# Zio_Qwiic_Eink_Display_Red_2_9.net
KiCad netlist of a schematic drawn in EAGLE
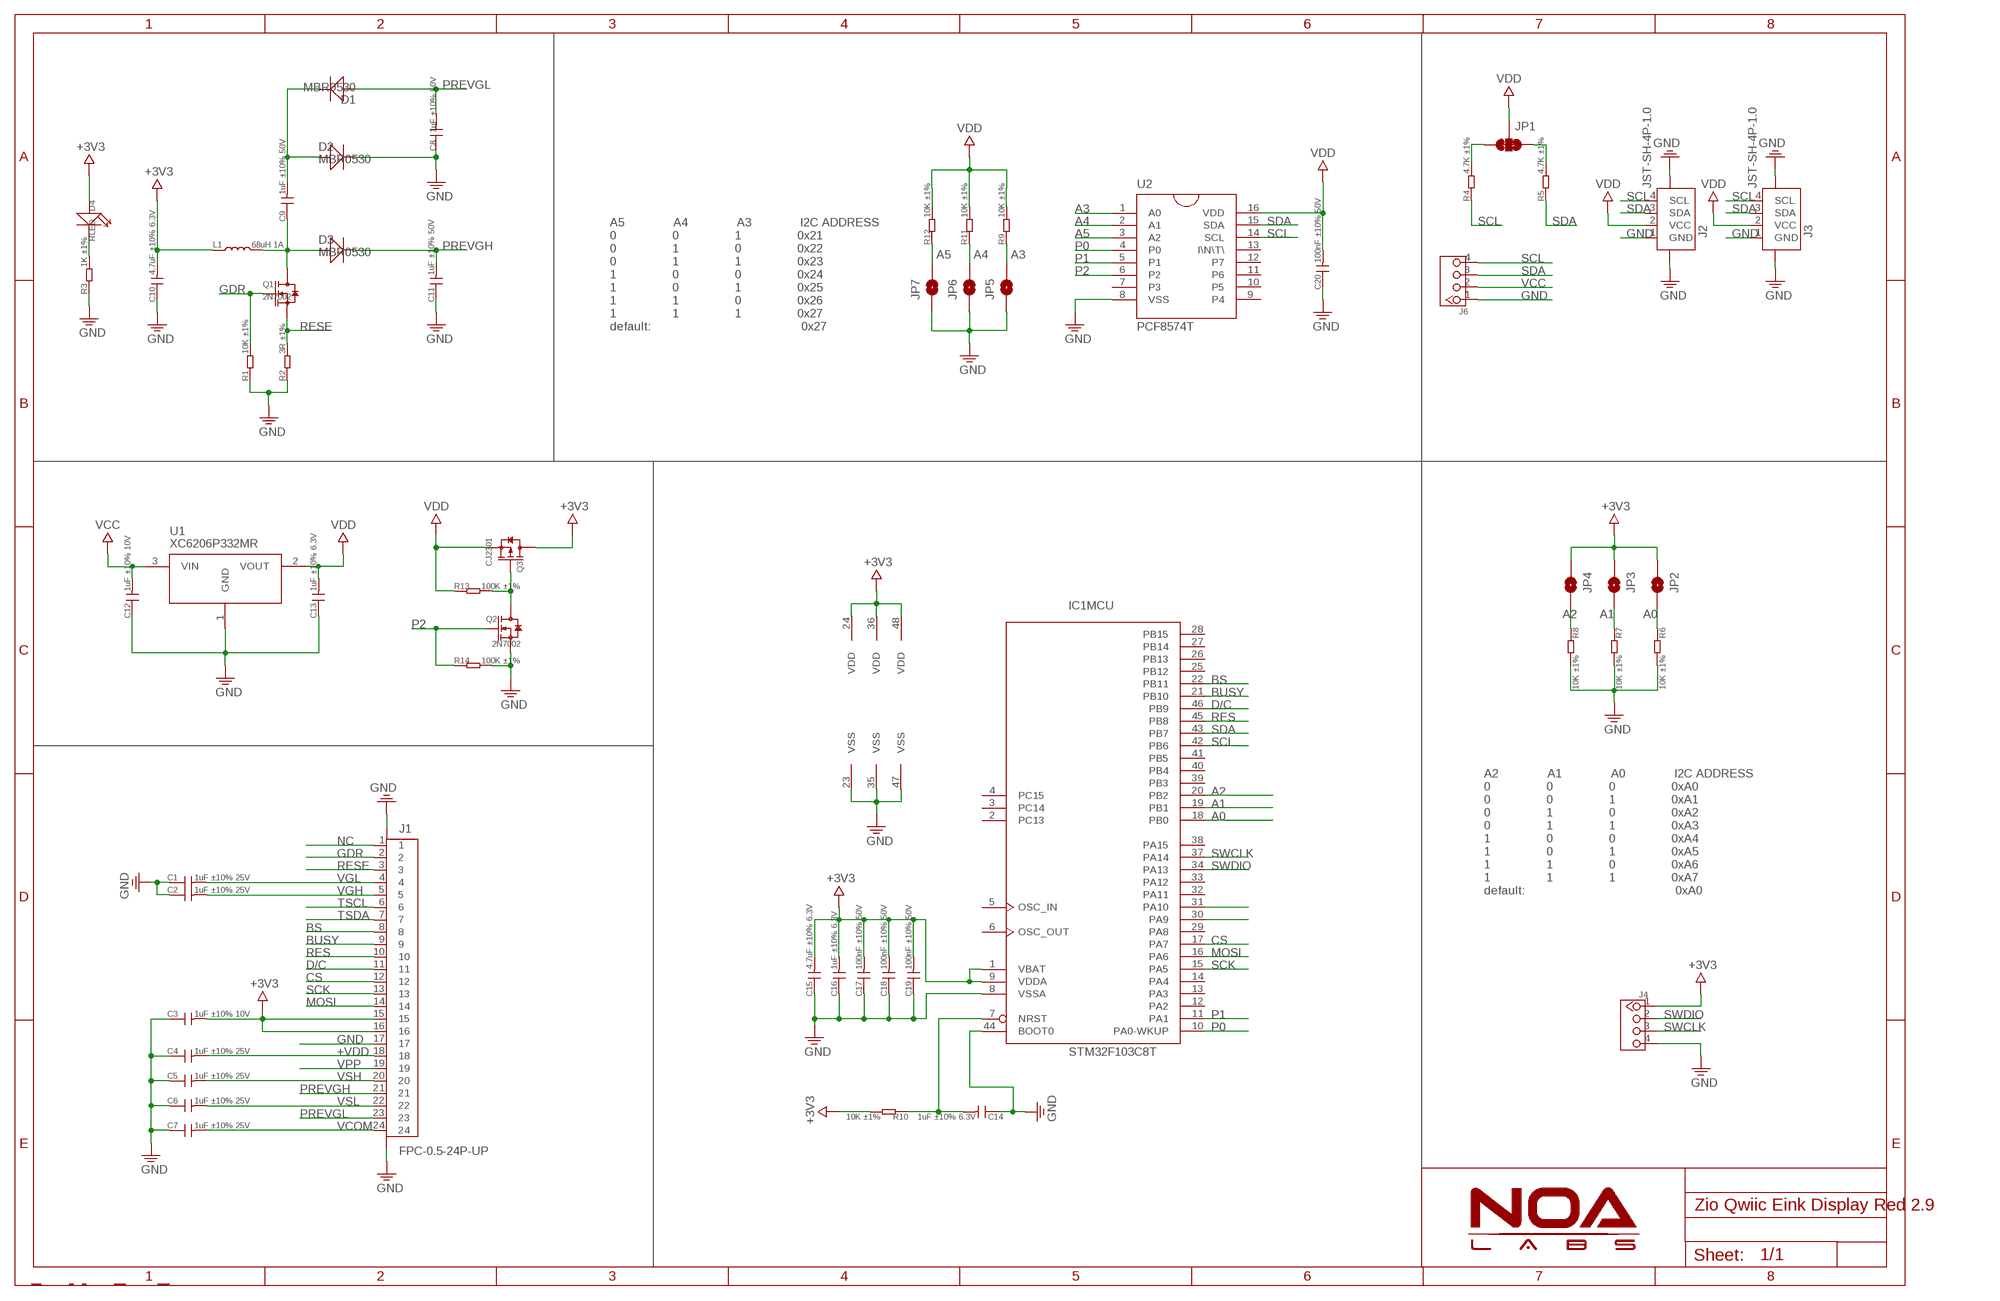
[diagram p0: schematic, sheet 1]

(export (version "E")
  (design (tool "Eeschema 10.0.6"))
  (components
    (comp (ref "C1")
      (value "1uF ±10% 25V")
      (footprint "eagle-import:C0603")
      (libsource (lib "eagle-import") (part "RCL_1838970_C-0603"))
    )
    (comp (ref "C2")
      (value "1uF ±10% 25V")
      (footprint "eagle-import:C0603")
      (libsource (lib "eagle-import") (part "RCL_1838970_C-0603"))
    )
    (comp (ref "C3")
      (value "1uF ±10% 10V")
      (footprint "eagle-import:C0603")
      (libsource (lib "eagle-import") (part "RCL_1838970_C-0603"))
    )
    (comp (ref "C4")
      (value "1uF ±10% 25V")
      (footprint "eagle-import:C0603")
      (libsource (lib "eagle-import") (part "RCL_1838970_C-0603"))
    )
    (comp (ref "C5")
      (value "1uF ±10% 25V")
      (footprint "eagle-import:C0603")
      (libsource (lib "eagle-import") (part "RCL_1838970_C-0603"))
    )
    (comp (ref "C6")
      (value "1uF ±10% 25V")
      (footprint "eagle-import:C0603")
      (libsource (lib "eagle-import") (part "RCL_1838970_C-0603"))
    )
    (comp (ref "C7")
      (value "1uF ±10% 25V")
      (footprint "eagle-import:C0603")
      (libsource (lib "eagle-import") (part "RCL_1838970_C-0603"))
    )
    (comp (ref "C8")
      (value "1uF ±10% 50V")
      (footprint "eagle-import:0603")
      (libsource (lib "eagle-import") (part "C-0603"))
    )
    (comp (ref "C9")
      (value "1uF ±10% 50V")
      (footprint "eagle-import:C0603")
      (libsource (lib "eagle-import") (part "RCL_1838970_C-0603"))
    )
    (comp (ref "C10")
      (value "4.7uF ±10% 6.3V")
      (footprint "eagle-import:C0603")
      (libsource (lib "eagle-import") (part "RCL_1838970_C-0603"))
    )
    (comp (ref "C11")
      (value "1uF ±10% 50V")
      (footprint "eagle-import:C0603")
      (libsource (lib "eagle-import") (part "RCL_1838970_C-0603"))
    )
    (comp (ref "C12")
      (value "1uF ±10% 10V")
      (footprint "eagle-import:C0603")
      (libsource (lib "eagle-import") (part "RCL_1838970_C-0603"))
    )
    (comp (ref "C13")
      (value "1uF ±10% 6.3V")
      (footprint "eagle-import:C0603")
      (libsource (lib "eagle-import") (part "RCL_1838970_C-0603"))
    )
    (comp (ref "C14")
      (value "1uF ±10% 6.3V")
      (footprint "eagle-import:C0603")
      (libsource (lib "eagle-import") (part "RCL_1838970_C-0603"))
    )
    (comp (ref "C15")
      (value "4.7uF ±10% 6.3V")
      (footprint "eagle-import:C0603")
      (libsource (lib "eagle-import") (part "RCL_1838970_C-0603"))
    )
    (comp (ref "C16")
      (value "1uF ±10% 6.3V")
      (footprint "eagle-import:C0603")
      (libsource (lib "eagle-import") (part "RCL_1838970_C-0603"))
    )
    (comp (ref "C17")
      (value "100nF ±10% 50V")
      (footprint "eagle-import:C0603")
      (libsource (lib "eagle-import") (part "RCL_1838970_C-0603"))
    )
    (comp (ref "C18")
      (value "100nF ±10% 50V")
      (footprint "eagle-import:C0603")
      (libsource (lib "eagle-import") (part "RCL_1838970_C-0603"))
    )
    (comp (ref "C19")
      (value "100nF ±10% 50V")
      (footprint "eagle-import:C0603")
      (libsource (lib "eagle-import") (part "RCL_1838970_C-0603"))
    )
    (comp (ref "C20")
      (value "100nF ±10% 50V")
      (footprint "eagle-import:C0603")
      (libsource (lib "eagle-import") (part "RCL_1838970_C-0603"))
    )
    (comp (ref "D1")
      (value "MBR0530")
      (footprint "eagle-import:SOD123")
      (libsource (lib "eagle-import") (part "D'1206'"))
    )
    (comp (ref "D2")
      (value "MBR0530")
      (footprint "eagle-import:SOD123")
      (libsource (lib "eagle-import") (part "D'1206'"))
    )
    (comp (ref "D3")
      (value "MBR0530")
      (footprint "eagle-import:SOD123")
      (libsource (lib "eagle-import") (part "D'1206'"))
    )
    (comp (ref "D4")
      (value "RLED")
      (footprint "eagle-import:LED-0603")
      (libsource (lib "eagle-import") (part "LED'0603'"))
    )
    (comp (ref "IC1")
      (value "STM32F103C8T")
      (footprint "eagle-import:LQFP48")
      (libsource (lib "eagle-import") (part "STM32F103CT8"))
    )
    (comp (ref "J1")
      (value "FPC-0.5-24P-UP")
      (footprint "eagle-import:FPC-0.5-24P_UP")
      (libsource (lib "eagle-import") (part "FPC-0.5-24P-UP"))
    )
    (comp (ref "J2")
      (value "JST-SH-4P-1.0")
      (footprint "eagle-import:JST-SH-4P")
      (libsource (lib "eagle-import") (part "JST-SH-4P-1.0"))
    )
    (comp (ref "J3")
      (value "JST-SH-4P-1.0")
      (footprint "eagle-import:JST-SH-4P")
      (libsource (lib "eagle-import") (part "JST-SH-4P-1.0"))
    )
    (comp (ref "J4")
      (value "HEADER-4P-2.54-SMD")
      (footprint "eagle-import:4P-2.54-SMD-180")
      (libsource (lib "eagle-import") (part "HEADER-4P-2.54-SMD"))
    )
    (comp (ref "J6")
      (value "HEADER-4P-60/35MIL")
      (footprint "eagle-import:4P-65_35MIL")
      (libsource (lib "eagle-import") (part "Connector_NOA_1982094_HEADER-4P-60/35MIL"))
    )
    (comp (ref "JP1")
      (value "SMT-JUMPER_3_2-NC_TRACE")
      (footprint "eagle-import:SMT-JUMPER_3_2-NC_TRACE")
      (libsource (lib "eagle-import") (part "SMT-JUMPER_3_2-NC_TRACE"))
    )
    (comp (ref "JP2")
      (value "JUMPER-SMT_2_NC_PASTE_NOCREM")
      (footprint "eagle-import:SMT-JUMPER_2_NC_PASTE_SILK_NOCREM")
      (libsource (lib "eagle-import") (part "JUMPER-SMT_2_NC_PASTE_NOCREM"))
    )
    (comp (ref "JP3")
      (value "JUMPER-SMT_2_NC_PASTE_NOCREM")
      (footprint "eagle-import:SMT-JUMPER_2_NC_PASTE_SILK_NOCREM")
      (libsource (lib "eagle-import") (part "JUMPER-SMT_2_NC_PASTE_NOCREM"))
    )
    (comp (ref "JP4")
      (value "JUMPER-SMT_2_NC_PASTE_NOCREM")
      (footprint "eagle-import:SMT-JUMPER_2_NC_PASTE_SILK_NOCREM")
      (libsource (lib "eagle-import") (part "JUMPER-SMT_2_NC_PASTE_NOCREM"))
    )
    (comp (ref "JP5")
      (value "JUMPER-SMT_2_NC_PASTE_NOCREM")
      (footprint "eagle-import:SMT-JUMPER_2_NC_PASTE_SILK_NOCREM")
      (libsource (lib "eagle-import") (part "JUMPER-SMT_2_NC_PASTE_NOCREM"))
    )
    (comp (ref "JP6")
      (value "JUMPER-SMT_2_NC_PASTE_NOCREM")
      (footprint "eagle-import:SMT-JUMPER_2_NC_PASTE_SILK_NOCREM")
      (libsource (lib "eagle-import") (part "JUMPER-SMT_2_NC_PASTE_NOCREM"))
    )
    (comp (ref "JP7")
      (value "JUMPER-SMT_2_NC_PASTE_NOCREM")
      (footprint "eagle-import:SMT-JUMPER_2_NC_PASTE_SILK_NOCREM")
      (libsource (lib "eagle-import") (part "JUMPER-SMT_2_NC_PASTE_NOCREM"))
    )
    (comp (ref "L1")
      (value "68uH 1A")
      (footprint "eagle-import:L3012")
      (libsource (lib "eagle-import") (part "L-3012"))
    )
    (comp (ref "Q1")
      (value "2N7002")
      (footprint "eagle-import:SOT23")
      (libsource (lib "eagle-import") (part "Discretex_MOSFET-N-SOT23"))
    )
    (comp (ref "Q2")
      (value "2N7002")
      (footprint "eagle-import:SOT23")
      (libsource (lib "eagle-import") (part "MOSFET-N-SOT23"))
    )
    (comp (ref "Q3")
      (value "CJ2301")
      (footprint "eagle-import:SOT23")
      (libsource (lib "eagle-import") (part "MOSFET-P-SOT23"))
    )
    (comp (ref "R1")
      (value "10K ±1%")
      (footprint "eagle-import:R0603")
      (libsource (lib "eagle-import") (part "R-0603"))
    )
    (comp (ref "R2")
      (value "3R ±1%")
      (footprint "eagle-import:R0603")
      (libsource (lib "eagle-import") (part "R-0603"))
    )
    (comp (ref "R3")
      (value "1K ±1%")
      (footprint "eagle-import:R0603")
      (libsource (lib "eagle-import") (part "R-0603"))
    )
    (comp (ref "R4")
      (value "4.7K ±1%")
      (footprint "eagle-import:R0603")
      (libsource (lib "eagle-import") (part "R-0603"))
    )
    (comp (ref "R5")
      (value "4.7K ±1%")
      (footprint "eagle-import:R0603")
      (libsource (lib "eagle-import") (part "R-0603"))
    )
    (comp (ref "R6")
      (value "10K ±1%")
      (footprint "eagle-import:R0603")
      (libsource (lib "eagle-import") (part "R-0603"))
    )
    (comp (ref "R7")
      (value "10K ±1%")
      (footprint "eagle-import:R0603")
      (libsource (lib "eagle-import") (part "R-0603"))
    )
    (comp (ref "R8")
      (value "10K ±1%")
      (footprint "eagle-import:R0603")
      (libsource (lib "eagle-import") (part "R-0603"))
    )
    (comp (ref "R9")
      (value "10K ±1%")
      (footprint "eagle-import:R0603")
      (libsource (lib "eagle-import") (part "R-0603"))
    )
    (comp (ref "R10")
      (value "10K ±1%")
      (footprint "eagle-import:R0603")
      (libsource (lib "eagle-import") (part "R-0603"))
    )
    (comp (ref "R11")
      (value "10K ±1%")
      (footprint "eagle-import:R0603")
      (libsource (lib "eagle-import") (part "R-0603"))
    )
    (comp (ref "R12")
      (value "10K ±1%")
      (footprint "eagle-import:R0603")
      (libsource (lib "eagle-import") (part "R-0603"))
    )
    (comp (ref "R13")
      (value "100K ±1%")
      (footprint "eagle-import:R0603")
      (libsource (lib "eagle-import") (part "R-0603"))
    )
    (comp (ref "R14")
      (value "100K ±1%")
      (footprint "eagle-import:R0603")
      (libsource (lib "eagle-import") (part "R-0603"))
    )
    (comp (ref "U1")
      (value "XC6206P332MR")
      (footprint "eagle-import:SOT23")
      (libsource (lib "eagle-import") (part "XC6206MR"))
    )
    (comp (ref "U2")
      (value "PCF8574T")
      (footprint "eagle-import:SO16-W")
      (libsource (lib "eagle-import") (part "PCF8574T"))
    )
  )
  (nets
    (net (code "1") (name "+3V3") (class "Default")
      (node (ref "C10") (pin "2") (pinfunction "2_2") (pintype "passive"))
      (node (ref "C15") (pin "2") (pinfunction "2_2") (pintype "passive"))
      (node (ref "C16") (pin "2") (pinfunction "2_2") (pintype "passive"))
      (node (ref "C17") (pin "2") (pinfunction "2_2") (pintype "passive"))
      (node (ref "C18") (pin "2") (pinfunction "2_2") (pintype "passive"))
      (node (ref "C19") (pin "2") (pinfunction "2_2") (pintype "passive"))
      (node (ref "C3") (pin "2") (pinfunction "2_2") (pintype "passive"))
      (node (ref "D4") (pin "+") (pinfunction "+_+") (pintype "passive"))
      (node (ref "IC1") (pin "1") (pinfunction "VBAT_1") (pintype "power_in"))
      (node (ref "IC1") (pin "24") (pinfunction "VDD_24") (pintype "power_in"))
      (node (ref "IC1") (pin "36") (pinfunction "VDD_36") (pintype "power_in"))
      (node (ref "IC1") (pin "48") (pinfunction "VDD_48") (pintype "power_in"))
      (node (ref "IC1") (pin "9") (pinfunction "VDDA_9") (pintype "power_in"))
      (node (ref "J1") (pin "15") (pinfunction "15_15") (pintype "bidirectional"))
      (node (ref "J1") (pin "16") (pinfunction "16_16") (pintype "bidirectional"))
      (node (ref "J4") (pin "1") (pinfunction "P$1_1") (pintype "bidirectional"))
      (node (ref "JP2") (pin "1") (pinfunction "1_1") (pintype "passive"))
      (node (ref "JP3") (pin "1") (pinfunction "1_1") (pintype "passive"))
      (node (ref "JP4") (pin "1") (pinfunction "1_1") (pintype "passive"))
      (node (ref "L1") (pin "1") (pinfunction "1_1") (pintype "passive"))
      (node (ref "Q3") (pin "3") (pinfunction "D_3") (pintype "passive"))
      (node (ref "R10") (pin "2") (pinfunction "2_2") (pintype "passive"))
    )
    (net (code "2") (name "/+VDD") (class "Default")
      (node (ref "C4") (pin "2") (pinfunction "2_2") (pintype "passive"))
      (node (ref "J1") (pin "18") (pinfunction "18_18") (pintype "bidirectional"))
    )
    (net (code "3") (name "/A0") (class "Default")
      (node (ref "IC1") (pin "18") (pinfunction "PB0_18") (pintype "bidirectional"))
      (node (ref "JP2") (pin "2") (pinfunction "2_2") (pintype "passive"))
      (node (ref "R6") (pin "1") (pinfunction "1_1") (pintype "passive"))
    )
    (net (code "4") (name "/A1") (class "Default")
      (node (ref "IC1") (pin "19") (pinfunction "PB1_19") (pintype "bidirectional"))
      (node (ref "JP3") (pin "2") (pinfunction "2_2") (pintype "passive"))
      (node (ref "R7") (pin "1") (pinfunction "1_1") (pintype "passive"))
    )
    (net (code "5") (name "/A2") (class "Default")
      (node (ref "IC1") (pin "20") (pinfunction "PB2_20") (pintype "bidirectional"))
      (node (ref "JP4") (pin "2") (pinfunction "2_2") (pintype "passive"))
      (node (ref "R8") (pin "1") (pinfunction "1_1") (pintype "passive"))
    )
    (net (code "6") (name "/A3") (class "Default")
      (node (ref "JP5") (pin "2") (pinfunction "2_2") (pintype "passive"))
      (node (ref "R9") (pin "1") (pinfunction "1_1") (pintype "passive"))
      (node (ref "U2") (pin "1") (pinfunction "A0_1") (pintype "bidirectional"))
    )
    (net (code "7") (name "/A4") (class "Default")
      (node (ref "JP6") (pin "2") (pinfunction "2_2") (pintype "passive"))
      (node (ref "R11") (pin "1") (pinfunction "1_1") (pintype "passive"))
      (node (ref "U2") (pin "2") (pinfunction "A1_2") (pintype "bidirectional"))
    )
    (net (code "8") (name "/A5") (class "Default")
      (node (ref "JP7") (pin "2") (pinfunction "2_2") (pintype "passive"))
      (node (ref "R12") (pin "1") (pinfunction "1_1") (pintype "passive"))
      (node (ref "U2") (pin "3") (pinfunction "A2_3") (pintype "bidirectional"))
    )
    (net (code "9") (name "/BS") (class "Default")
      (node (ref "IC1") (pin "22") (pinfunction "PB11_22") (pintype "bidirectional"))
      (node (ref "J1") (pin "8") (pinfunction "8_8") (pintype "bidirectional"))
    )
    (net (code "10") (name "/BUSY") (class "Default")
      (node (ref "IC1") (pin "21") (pinfunction "PB10_21") (pintype "bidirectional"))
      (node (ref "J1") (pin "9") (pinfunction "9_9") (pintype "bidirectional"))
    )
    (net (code "11") (name "/CS") (class "Default")
      (node (ref "IC1") (pin "17") (pinfunction "PA7_17") (pintype "bidirectional"))
      (node (ref "J1") (pin "12") (pinfunction "12_12") (pintype "bidirectional"))
    )
    (net (code "12") (name "/D{slash}C") (class "Default")
      (node (ref "IC1") (pin "46") (pinfunction "PB9_46") (pintype "bidirectional"))
      (node (ref "J1") (pin "11") (pinfunction "11_11") (pintype "bidirectional"))
    )
    (net (code "13") (name "/GDR") (class "Default")
      (node (ref "J1") (pin "2") (pinfunction "2_2") (pintype "bidirectional"))
      (node (ref "Q1") (pin "1") (pinfunction "G_1") (pintype "passive"))
      (node (ref "R1") (pin "2") (pinfunction "2_2") (pintype "passive"))
    )
    (net (code "14") (name "/MOSI") (class "Default")
      (node (ref "IC1") (pin "16") (pinfunction "PA6_16") (pintype "bidirectional"))
      (node (ref "J1") (pin "14") (pinfunction "14_14") (pintype "bidirectional"))
    )
    (net (code "15") (name "/NC") (class "Default")
      (node (ref "J1") (pin "1") (pinfunction "1_1") (pintype "bidirectional"))
    )
    (net (code "16") (name "/P0") (class "Default")
      (node (ref "IC1") (pin "10") (pinfunction "PA0-WKUP_10") (pintype "bidirectional"))
      (node (ref "U2") (pin "4") (pinfunction "P0_4") (pintype "bidirectional"))
    )
    (net (code "17") (name "/P1") (class "Default")
      (node (ref "IC1") (pin "11") (pinfunction "PA1_11") (pintype "bidirectional"))
      (node (ref "U2") (pin "5") (pinfunction "P1_5") (pintype "bidirectional"))
    )
    (net (code "18") (name "/P2") (class "Default")
      (node (ref "Q2") (pin "1") (pinfunction "G_1") (pintype "passive"))
      (node (ref "R14") (pin "1") (pinfunction "1_1") (pintype "passive"))
      (node (ref "U2") (pin "6") (pinfunction "P2_6") (pintype "bidirectional"))
    )
    (net (code "19") (name "/PREVGH") (class "Default")
      (node (ref "C11") (pin "2") (pinfunction "2_2") (pintype "passive"))
      (node (ref "D3") (pin "-") (pinfunction "-_-") (pintype "passive"))
      (node (ref "J1") (pin "21") (pinfunction "21_21") (pintype "bidirectional"))
    )
    (net (code "20") (name "/PREVGL") (class "Default")
      (node (ref "C8") (pin "2") (pinfunction "2_2") (pintype "passive"))
      (node (ref "D1") (pin "+") (pinfunction "+_+") (pintype "passive"))
      (node (ref "J1") (pin "23") (pinfunction "23_23") (pintype "bidirectional"))
    )
    (net (code "21") (name "/RES") (class "Default")
      (node (ref "IC1") (pin "45") (pinfunction "PB8_45") (pintype "bidirectional"))
      (node (ref "J1") (pin "10") (pinfunction "10_10") (pintype "bidirectional"))
    )
    (net (code "22") (name "/RESE") (class "Default")
      (node (ref "J1") (pin "3") (pinfunction "3_3") (pintype "bidirectional"))
      (node (ref "Q1") (pin "2") (pinfunction "S_2") (pintype "passive"))
      (node (ref "R2") (pin "2") (pinfunction "2_2") (pintype "passive"))
    )
    (net (code "23") (name "/SCK") (class "Default")
      (node (ref "IC1") (pin "15") (pinfunction "PA5_15") (pintype "bidirectional"))
      (node (ref "J1") (pin "13") (pinfunction "13_13") (pintype "bidirectional"))
    )
    (net (code "24") (name "/SCL") (class "Default")
      (node (ref "IC1") (pin "42") (pinfunction "PB6_42") (pintype "bidirectional"))
      (node (ref "J2") (pin "4") (pinfunction "SCL_4") (pintype "bidirectional"))
      (node (ref "J3") (pin "4") (pinfunction "SCL_4") (pintype "bidirectional"))
      (node (ref "J6") (pin "4") (pinfunction "P$4_4") (pintype "bidirectional"))
      (node (ref "R4") (pin "1") (pinfunction "1_1") (pintype "passive"))
      (node (ref "U2") (pin "14") (pinfunction "SCL_14") (pintype "bidirectional"))
    )
    (net (code "25") (name "/SDA") (class "Default")
      (node (ref "IC1") (pin "43") (pinfunction "PB7_43") (pintype "bidirectional"))
      (node (ref "J2") (pin "3") (pinfunction "SDA_3") (pintype "bidirectional"))
      (node (ref "J3") (pin "3") (pinfunction "SDA_3") (pintype "bidirectional"))
      (node (ref "J6") (pin "3") (pinfunction "P$3_3") (pintype "bidirectional"))
      (node (ref "R5") (pin "1") (pinfunction "1_1") (pintype "passive"))
      (node (ref "U2") (pin "15") (pinfunction "SDA_15") (pintype "bidirectional"))
    )
    (net (code "26") (name "/SWCLK") (class "Default")
      (node (ref "IC1") (pin "37") (pinfunction "PA14_37") (pintype "bidirectional"))
      (node (ref "J4") (pin "3") (pinfunction "P$3_3") (pintype "bidirectional"))
    )
    (net (code "27") (name "/SWDIO") (class "Default")
      (node (ref "IC1") (pin "34") (pinfunction "PA13_34") (pintype "bidirectional"))
      (node (ref "J4") (pin "2") (pinfunction "P$2_2") (pintype "bidirectional"))
    )
    (net (code "28") (name "/TSCL") (class "Default")
      (node (ref "J1") (pin "6") (pinfunction "6_6") (pintype "bidirectional"))
    )
    (net (code "29") (name "/TSDA") (class "Default")
      (node (ref "J1") (pin "7") (pinfunction "7_7") (pintype "bidirectional"))
    )
    (net (code "30") (name "/VCOM") (class "Default")
      (node (ref "C7") (pin "2") (pinfunction "2_2") (pintype "passive"))
      (node (ref "J1") (pin "24") (pinfunction "24_24") (pintype "bidirectional"))
    )
    (net (code "31") (name "/VGH") (class "Default")
      (node (ref "C2") (pin "2") (pinfunction "2_2") (pintype "passive"))
      (node (ref "J1") (pin "5") (pinfunction "5_5") (pintype "bidirectional"))
    )
    (net (code "32") (name "/VGL") (class "Default")
      (node (ref "C1") (pin "2") (pinfunction "2_2") (pintype "passive"))
      (node (ref "J1") (pin "4") (pinfunction "4_4") (pintype "bidirectional"))
    )
    (net (code "33") (name "/VPP") (class "Default")
      (node (ref "J1") (pin "19") (pinfunction "19_19") (pintype "bidirectional"))
    )
    (net (code "34") (name "/VSH") (class "Default")
      (node (ref "C5") (pin "2") (pinfunction "2_2") (pintype "passive"))
      (node (ref "J1") (pin "20") (pinfunction "20_20") (pintype "bidirectional"))
    )
    (net (code "35") (name "/VSL") (class "Default")
      (node (ref "C6") (pin "2") (pinfunction "2_2") (pintype "passive"))
      (node (ref "J1") (pin "22") (pinfunction "22_22") (pintype "bidirectional"))
    )
    (net (code "36") (name "GND") (class "Default")
      (node (ref "C1") (pin "1") (pinfunction "1_1") (pintype "passive"))
      (node (ref "C10") (pin "1") (pinfunction "1_1") (pintype "passive"))
      (node (ref "C11") (pin "1") (pinfunction "1_1") (pintype "passive"))
      (node (ref "C12") (pin "1") (pinfunction "1_1") (pintype "passive"))
      (node (ref "C13") (pin "1") (pinfunction "1_1") (pintype "passive"))
      (node (ref "C14") (pin "1") (pinfunction "1_1") (pintype "passive"))
      (node (ref "C15") (pin "1") (pinfunction "1_1") (pintype "passive"))
      (node (ref "C16") (pin "1") (pinfunction "1_1") (pintype "passive"))
      (node (ref "C17") (pin "1") (pinfunction "1_1") (pintype "passive"))
      (node (ref "C18") (pin "1") (pinfunction "1_1") (pintype "passive"))
      (node (ref "C19") (pin "1") (pinfunction "1_1") (pintype "passive"))
      (node (ref "C2") (pin "1") (pinfunction "1_1") (pintype "passive"))
      (node (ref "C20") (pin "1") (pinfunction "1_1") (pintype "passive"))
      (node (ref "C3") (pin "1") (pinfunction "1_1") (pintype "passive"))
      (node (ref "C4") (pin "1") (pinfunction "1_1") (pintype "passive"))
      (node (ref "C5") (pin "1") (pinfunction "1_1") (pintype "passive"))
      (node (ref "C6") (pin "1") (pinfunction "1_1") (pintype "passive"))
      (node (ref "C7") (pin "1") (pinfunction "1_1") (pintype "passive"))
      (node (ref "C8") (pin "1") (pinfunction "1_1") (pintype "passive"))
      (node (ref "D2") (pin "-") (pinfunction "-_-") (pintype "passive"))
      (node (ref "IC1") (pin "23") (pinfunction "VSS_23") (pintype "power_in"))
      (node (ref "IC1") (pin "35") (pinfunction "VSS_35") (pintype "power_in"))
      (node (ref "IC1") (pin "44") (pinfunction "BOOT0_44") (pintype "input"))
      (node (ref "IC1") (pin "47") (pinfunction "VSS_47") (pintype "power_in"))
      (node (ref "IC1") (pin "8") (pinfunction "VSSA_8") (pintype "power_in"))
      (node (ref "J1") (pin "17") (pinfunction "17_17") (pintype "bidirectional"))
      (node (ref "J1") (pin "25") (pinfunction "G1_25") (pintype "bidirectional"))
      (node (ref "J1") (pin "26") (pinfunction "G2_26") (pintype "bidirectional"))
      (node (ref "J2") (pin "1") (pinfunction "GND_1") (pintype "bidirectional"))
      (node (ref "J2") (pin "NC1") (pinfunction "5_NC1") (pintype "bidirectional"))
      (node (ref "J2") (pin "NC2") (pinfunction "6_NC2") (pintype "bidirectional"))
      (node (ref "J3") (pin "1") (pinfunction "GND_1") (pintype "bidirectional"))
      (node (ref "J3") (pin "NC1") (pinfunction "5_NC1") (pintype "bidirectional"))
      (node (ref "J3") (pin "NC2") (pinfunction "6_NC2") (pintype "bidirectional"))
      (node (ref "J4") (pin "4") (pinfunction "P$4_4") (pintype "bidirectional"))
      (node (ref "J6") (pin "1") (pinfunction "P$1_1") (pintype "bidirectional"))
      (node (ref "JP5") (pin "1") (pinfunction "1_1") (pintype "passive"))
      (node (ref "JP6") (pin "1") (pinfunction "1_1") (pintype "passive"))
      (node (ref "JP7") (pin "1") (pinfunction "1_1") (pintype "passive"))
      (node (ref "Q2") (pin "2") (pinfunction "S_2") (pintype "passive"))
      (node (ref "R1") (pin "1") (pinfunction "1_1") (pintype "passive"))
      (node (ref "R14") (pin "2") (pinfunction "2_2") (pintype "passive"))
      (node (ref "R2") (pin "1") (pinfunction "1_1") (pintype "passive"))
      (node (ref "R3") (pin "1") (pinfunction "1_1") (pintype "passive"))
      (node (ref "R6") (pin "2") (pinfunction "2_2") (pintype "passive"))
      (node (ref "R7") (pin "2") (pinfunction "2_2") (pintype "passive"))
      (node (ref "R8") (pin "2") (pinfunction "2_2") (pintype "passive"))
      (node (ref "U1") (pin "1") (pinfunction "GND_1") (pintype "bidirectional"))
      (node (ref "U2") (pin "8") (pinfunction "VSS_8") (pintype "bidirectional"))
    )
    (net (code "37") (name "Net-(C9-Pad2)") (class "Default")
      (node (ref "C9") (pin "2") (pinfunction "2_2") (pintype "passive"))
      (node (ref "D1") (pin "-") (pinfunction "-_-") (pintype "passive"))
      (node (ref "D2") (pin "+") (pinfunction "+_+") (pintype "passive"))
    )
    (net (code "38") (name "Net-(D4-Pad-)") (class "Default")
      (node (ref "D4") (pin "-") (pinfunction "-_-") (pintype "passive"))
      (node (ref "R3") (pin "2") (pinfunction "2_2") (pintype "passive"))
    )
    (net (code "39") (name "Net-(IC1B-NRST)") (class "Default")
      (node (ref "C14") (pin "2") (pinfunction "2_2") (pintype "passive"))
      (node (ref "IC1") (pin "7") (pinfunction "NRST_7") (pintype "bidirectional"))
      (node (ref "R10") (pin "1") (pinfunction "1_1") (pintype "passive"))
    )
    (net (code "40") (name "Net-(JP1-Pad1)") (class "Default")
      (node (ref "JP1") (pin "1") (pinfunction "1_1") (pintype "passive"))
      (node (ref "R5") (pin "2") (pinfunction "2_2") (pintype "passive"))
    )
    (net (code "41") (name "Net-(JP1-Pad3)") (class "Default")
      (node (ref "JP1") (pin "3") (pinfunction "3_3") (pintype "passive"))
      (node (ref "R4") (pin "2") (pinfunction "2_2") (pintype "passive"))
    )
    (net (code "42") (name "Net-(Q1-D)") (class "Default")
      (node (ref "C9") (pin "1") (pinfunction "1_1") (pintype "passive"))
      (node (ref "D3") (pin "+") (pinfunction "+_+") (pintype "passive"))
      (node (ref "L1") (pin "2") (pinfunction "2_2") (pintype "passive"))
      (node (ref "Q1") (pin "3") (pinfunction "D_3") (pintype "passive"))
    )
    (net (code "43") (name "Net-(Q2-D)") (class "Default")
      (node (ref "Q2") (pin "3") (pinfunction "D_3") (pintype "passive"))
      (node (ref "Q3") (pin "1") (pinfunction "G_1") (pintype "passive"))
      (node (ref "R13") (pin "2") (pinfunction "2_2") (pintype "passive"))
    )
    (net (code "44") (name "VCC") (class "Default")
      (node (ref "C12") (pin "2") (pinfunction "2_2") (pintype "passive"))
      (node (ref "J6") (pin "2") (pinfunction "P$2_2") (pintype "bidirectional"))
      (node (ref "U1") (pin "3") (pinfunction "VIN_3") (pintype "bidirectional"))
    )
    (net (code "45") (name "VDD") (class "Default")
      (node (ref "C13") (pin "2") (pinfunction "2_2") (pintype "passive"))
      (node (ref "C20") (pin "2") (pinfunction "2_2") (pintype "passive"))
      (node (ref "J2") (pin "2") (pinfunction "VCC_2") (pintype "bidirectional"))
      (node (ref "J3") (pin "2") (pinfunction "VCC_2") (pintype "bidirectional"))
      (node (ref "JP1") (pin "2") (pinfunction "2_2") (pintype "passive"))
      (node (ref "Q3") (pin "2") (pinfunction "S_2") (pintype "passive"))
      (node (ref "R11") (pin "2") (pinfunction "2_2") (pintype "passive"))
      (node (ref "R12") (pin "2") (pinfunction "2_2") (pintype "passive"))
      (node (ref "R13") (pin "1") (pinfunction "1_1") (pintype "passive"))
      (node (ref "R9") (pin "2") (pinfunction "2_2") (pintype "passive"))
      (node (ref "U1") (pin "2") (pinfunction "VOUT_2") (pintype "bidirectional"))
      (node (ref "U2") (pin "16") (pinfunction "VDD_16") (pintype "bidirectional"))
    )
    (net (code "46") (name "unconnected-(IC1B-OSC_IN-Pad5)") (class "Default")
      (node (ref "IC1") (pin "5") (pinfunction "OSC_IN_5") (pintype "bidirectional"))
    )
    (net (code "47") (name "unconnected-(IC1B-OSC_OUT-Pad6)") (class "Default")
      (node (ref "IC1") (pin "6") (pinfunction "OSC_OUT_6") (pintype "bidirectional"))
    )
    (net (code "48") (name "unconnected-(IC1B-PA2-Pad12)") (class "Default")
      (node (ref "IC1") (pin "12") (pinfunction "PA2_12") (pintype "bidirectional"))
    )
    (net (code "49") (name "unconnected-(IC1B-PA3-Pad13)") (class "Default")
      (node (ref "IC1") (pin "13") (pinfunction "PA3_13") (pintype "bidirectional"))
    )
    (net (code "50") (name "unconnected-(IC1B-PA4-Pad14)") (class "Default")
      (node (ref "IC1") (pin "14") (pinfunction "PA4_14") (pintype "bidirectional"))
    )
    (net (code "51") (name "unconnected-(IC1B-PA8-Pad29)") (class "Default")
      (node (ref "IC1") (pin "29") (pinfunction "PA8_29") (pintype "bidirectional"))
    )
    (net (code "52") (name "unconnected-(IC1B-PA9-Pad30)") (class "Default")
      (node (ref "IC1") (pin "30") (pinfunction "PA9_30") (pintype "bidirectional"))
    )
    (net (code "53") (name "unconnected-(IC1B-PA10-Pad31)") (class "Default")
      (node (ref "IC1") (pin "31") (pinfunction "PA10_31") (pintype "bidirectional"))
    )
    (net (code "54") (name "unconnected-(IC1B-PA11-Pad32)") (class "Default")
      (node (ref "IC1") (pin "32") (pinfunction "PA11_32") (pintype "bidirectional"))
    )
    (net (code "55") (name "unconnected-(IC1B-PA12-Pad33)") (class "Default")
      (node (ref "IC1") (pin "33") (pinfunction "PA12_33") (pintype "bidirectional"))
    )
    (net (code "56") (name "unconnected-(IC1B-PA15-Pad38)") (class "Default")
      (node (ref "IC1") (pin "38") (pinfunction "PA15_38") (pintype "bidirectional"))
    )
    (net (code "57") (name "unconnected-(IC1B-PB3-Pad39)") (class "Default")
      (node (ref "IC1") (pin "39") (pinfunction "PB3_39") (pintype "bidirectional"))
    )
    (net (code "58") (name "unconnected-(IC1B-PB4-Pad40)") (class "Default")
      (node (ref "IC1") (pin "40") (pinfunction "PB4_40") (pintype "bidirectional"))
    )
    (net (code "59") (name "unconnected-(IC1B-PB5-Pad41)") (class "Default")
      (node (ref "IC1") (pin "41") (pinfunction "PB5_41") (pintype "bidirectional"))
    )
    (net (code "60") (name "unconnected-(IC1B-PB12-Pad25)") (class "Default")
      (node (ref "IC1") (pin "25") (pinfunction "PB12_25") (pintype "bidirectional"))
    )
    (net (code "61") (name "unconnected-(IC1B-PB13-Pad26)") (class "Default")
      (node (ref "IC1") (pin "26") (pinfunction "PB13_26") (pintype "bidirectional"))
    )
    (net (code "62") (name "unconnected-(IC1B-PB14-Pad27)") (class "Default")
      (node (ref "IC1") (pin "27") (pinfunction "PB14_27") (pintype "bidirectional"))
    )
    (net (code "63") (name "unconnected-(IC1B-PB15-Pad28)") (class "Default")
      (node (ref "IC1") (pin "28") (pinfunction "PB15_28") (pintype "bidirectional"))
    )
    (net (code "64") (name "unconnected-(IC1B-PC13-Pad2)") (class "Default")
      (node (ref "IC1") (pin "2") (pinfunction "PC13_2") (pintype "bidirectional"))
    )
    (net (code "65") (name "unconnected-(IC1B-PC14-Pad3)") (class "Default")
      (node (ref "IC1") (pin "3") (pinfunction "PC14_3") (pintype "bidirectional"))
    )
    (net (code "66") (name "unconnected-(IC1B-PC15-Pad4)") (class "Default")
      (node (ref "IC1") (pin "4") (pinfunction "PC15_4") (pintype "bidirectional"))
    )
    (net (code "67") (name "unconnected-(U2-I\\N\\T\\-Pad13)") (class "Default")
      (node (ref "U2") (pin "13") (pinfunction "I\\N\\T\\_13") (pintype "bidirectional"))
    )
    (net (code "68") (name "unconnected-(U2-P3-Pad7)") (class "Default")
      (node (ref "U2") (pin "7") (pinfunction "P3_7") (pintype "bidirectional"))
    )
    (net (code "69") (name "unconnected-(U2-P4-Pad9)") (class "Default")
      (node (ref "U2") (pin "9") (pinfunction "P4_9") (pintype "bidirectional"))
    )
    (net (code "70") (name "unconnected-(U2-P5-Pad10)") (class "Default")
      (node (ref "U2") (pin "10") (pinfunction "P5_10") (pintype "bidirectional"))
    )
    (net (code "71") (name "unconnected-(U2-P6-Pad11)") (class "Default")
      (node (ref "U2") (pin "11") (pinfunction "P6_11") (pintype "bidirectional"))
    )
    (net (code "72") (name "unconnected-(U2-P7-Pad12)") (class "Default")
      (node (ref "U2") (pin "12") (pinfunction "P7_12") (pintype "bidirectional"))
    )
  )
)
